# S7_Misc.net
KiCad netlist of a schematic drawn in Altium Designer
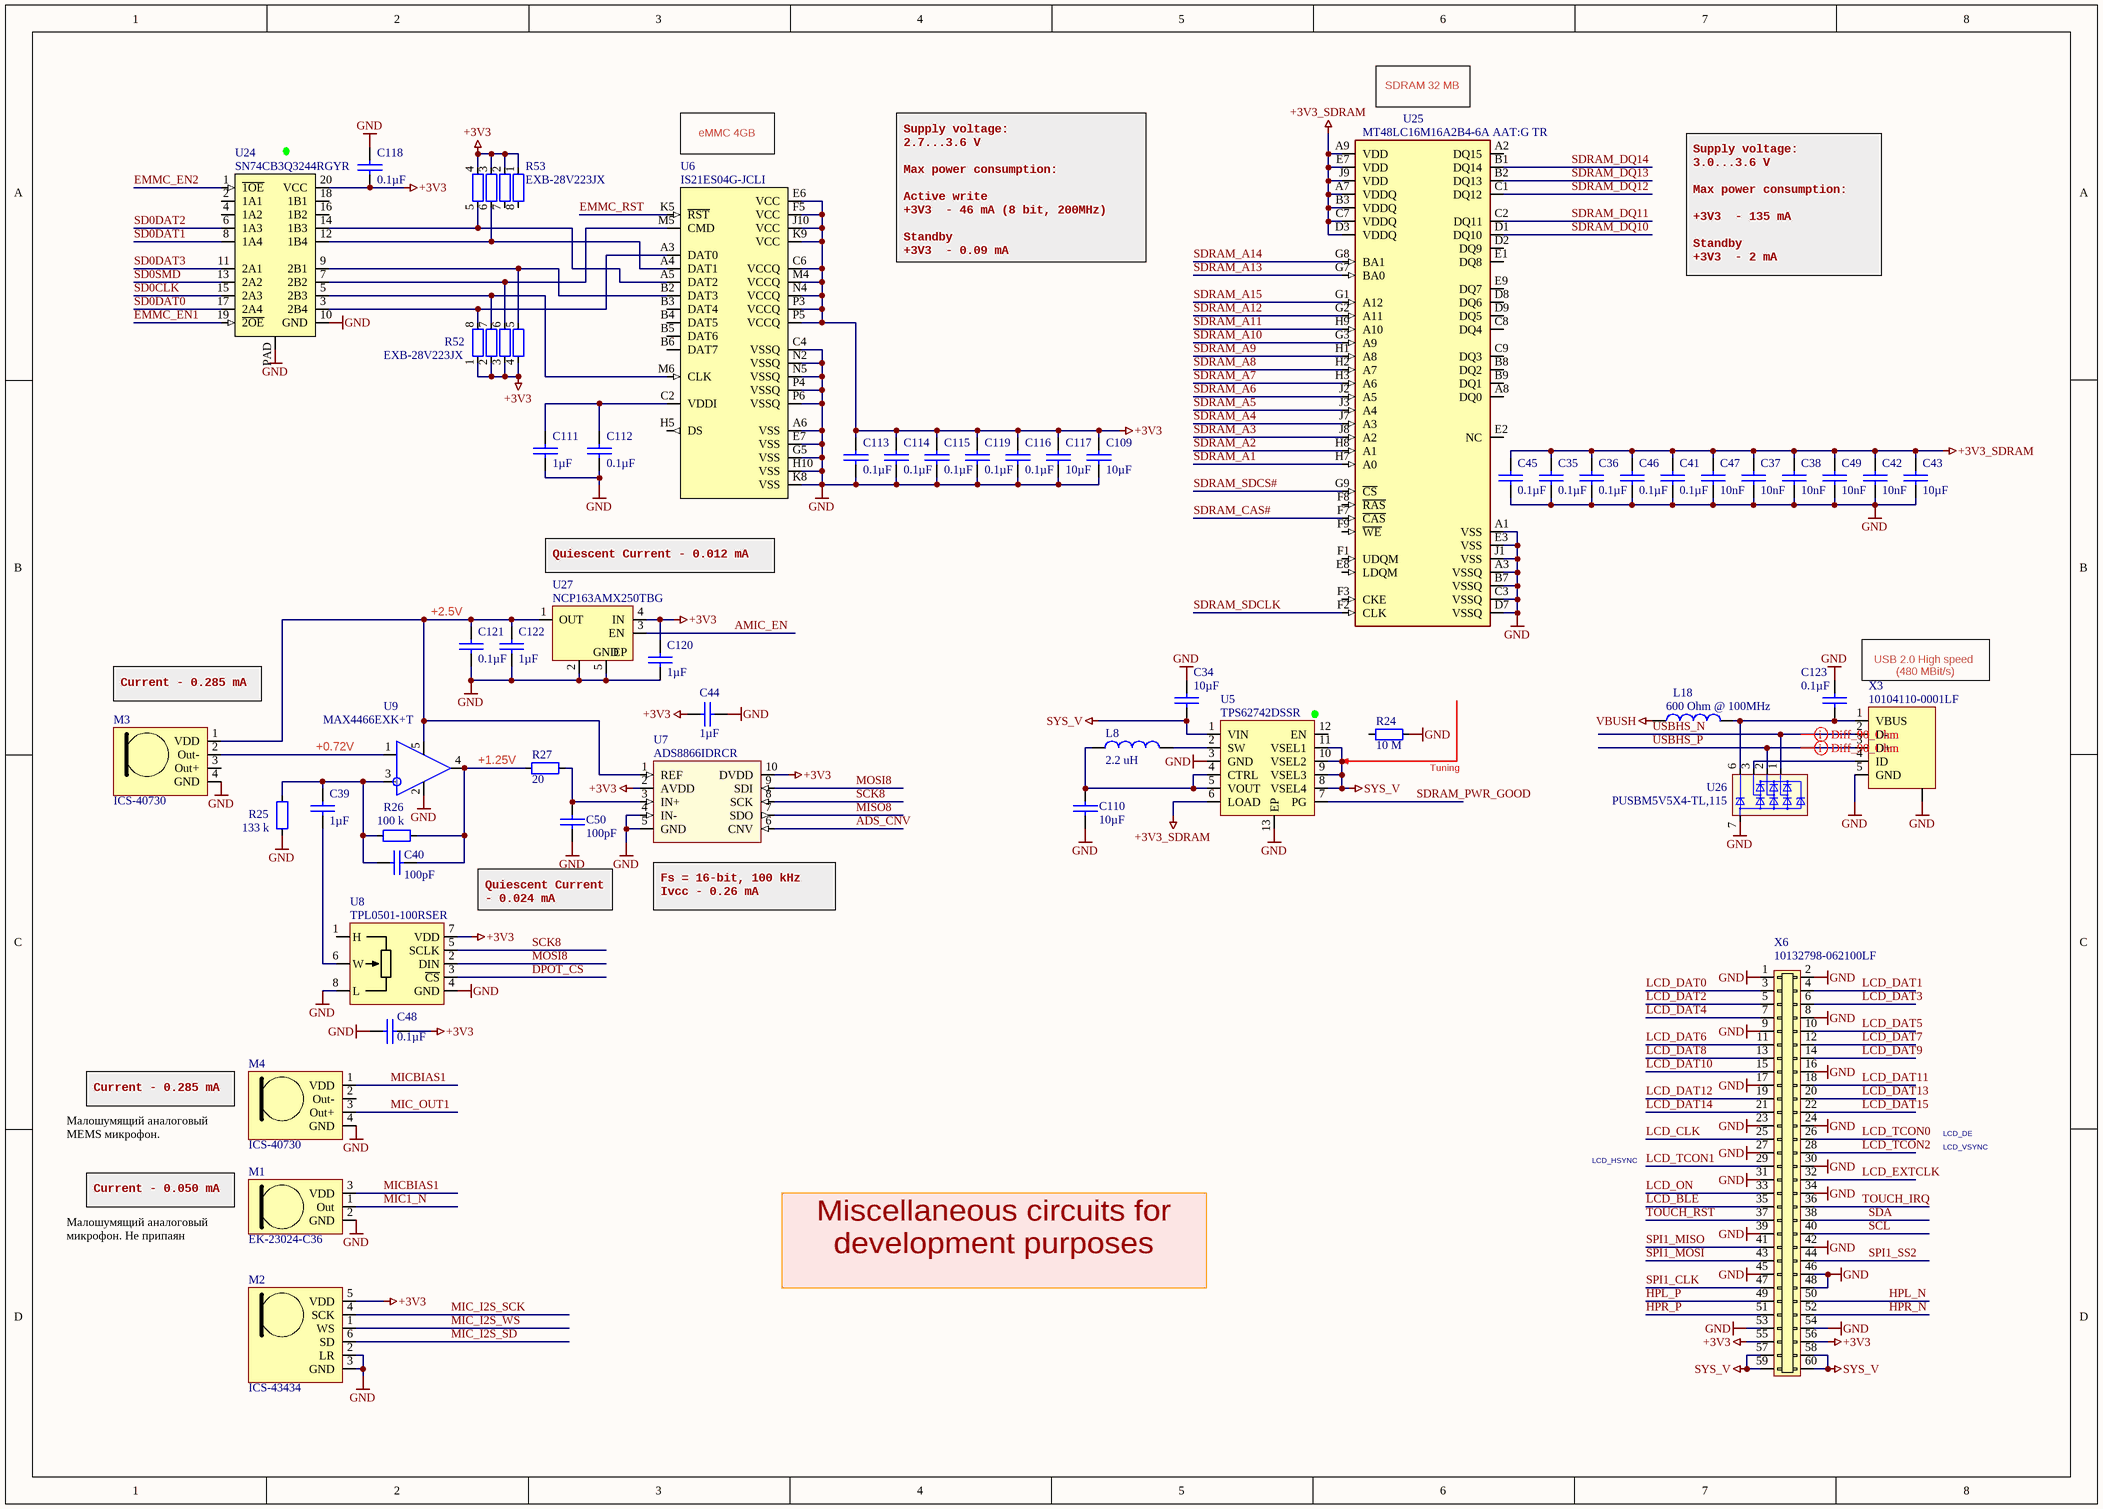
[diagram p0: S7_Misc.SchDoc]

(export (version "E")
  (design (tool "Eeschema 10.0.6"))
  (components
    (comp (ref "C34")
      (value "10µF")
      (footprint "0603 CAP")
      (description "10µF, ±10%, 16V, X5R, 0603 (1608 Metric), -55°C ~ 85°C, -, Automotive")
      (fields
        (field (name "PART NUMBER") "GRT188R61C106KE13D")
        (field (name "MANUFACTURER") "Murata Electronics North America")
      )
      (libsource (lib "ea_PassivComps") (part "Capacitor"))
    )
    (comp (ref "C35")
      (value "0.1µF")
      (footprint "0402 CAP")
      (description "0.1µF, ±10%, 50V, X7R, 0402 (1005 Metric), -55°C ~ 125°C, -, General Purpose")
      (fields
        (field (name "PART NUMBER") "0402B104K500CT")
        (field (name "MANUFACTURER") "Walsin Technology Corporation")
      )
      (libsource (lib "ea_PassivComps") (part "Capacitor"))
    )
    (comp (ref "C36")
      (value "0.1µF")
      (footprint "0402 CAP")
      (description "0.1µF, ±10%, 50V, X7R, 0402 (1005 Metric), -55°C ~ 125°C, -, General Purpose")
      (fields
        (field (name "PART NUMBER") "0402B104K500CT")
        (field (name "MANUFACTURER") "Walsin Technology Corporation")
      )
      (libsource (lib "ea_PassivComps") (part "Capacitor"))
    )
    (comp (ref "C37")
      (value "10nF")
      (footprint "0402 CAP")
      (description "10000pF, ±10%, 50V, X7R, 0402 (1005 Metric), -55°C ~ 125°C, -, General Purpose")
      (fields
        (field (name "PART NUMBER") "CL05B103KB5NNNC")
        (field (name "MANUFACTURER") "Samsung Electro-Mechanics")
      )
      (libsource (lib "ea_PassivComps") (part "Capacitor"))
    )
    (comp (ref "C38")
      (value "10nF")
      (footprint "0402 CAP")
      (description "10000pF, ±10%, 50V, X7R, 0402 (1005 Metric), -55°C ~ 125°C, -, General Purpose")
      (fields
        (field (name "PART NUMBER") "CL05B103KB5NNNC")
        (field (name "MANUFACTURER") "Samsung Electro-Mechanics")
      )
      (libsource (lib "ea_PassivComps") (part "Capacitor"))
    )
    (comp (ref "C39")
      (value "1µF")
      (footprint "0402 CAP")
      (description "1µF, ±20%, 25V, X5R, 0402 (1005 Metric), -55°C ~ 85°C, -, General Purpose")
      (fields (field (name "PART NUMBER") "TMK105BJ105MV-F") (field (name "MANUFACTURER") "Taiyo Yuden"))
      (libsource (lib "ea_PassivComps") (part "Capacitor"))
    )
    (comp (ref "C40")
      (value "100pF")
      (footprint "0402 CAP")
      (description "100pF, ±5%, 50V, C0G, NP0, 0402 (1005 Metric), -55°C ~ 125°C, -, Automotive")
      (fields (field (name "PART NUMBER") "AC0402JRNPO9BN101") (field (name "MANUFACTURER") "Yageo"))
      (libsource (lib "ea_PassivComps") (part "Capacitor"))
    )
    (comp (ref "C41")
      (value "0.1µF")
      (footprint "0402 CAP")
      (description "0.1µF, ±10%, 50V, X7R, 0402 (1005 Metric), -55°C ~ 125°C, -, General Purpose")
      (fields
        (field (name "PART NUMBER") "0402B104K500CT")
        (field (name "MANUFACTURER") "Walsin Technology Corporation")
      )
      (libsource (lib "ea_PassivComps") (part "Capacitor"))
    )
    (comp (ref "C42")
      (value "10nF")
      (footprint "0402 CAP")
      (description "10000pF, ±10%, 50V, X7R, 0402 (1005 Metric), -55°C ~ 125°C, -, General Purpose")
      (fields
        (field (name "PART NUMBER") "CL05B103KB5NNNC")
        (field (name "MANUFACTURER") "Samsung Electro-Mechanics")
      )
      (libsource (lib "ea_PassivComps") (part "Capacitor"))
    )
    (comp (ref "C43")
      (value "10µF")
      (footprint "0603 CAP")
      (description "10µF, ±10%, 16V, X5R, 0603 (1608 Metric), -55°C ~ 85°C, -, Automotive")
      (fields
        (field (name "PART NUMBER") "GRT188R61C106KE13D")
        (field (name "MANUFACTURER") "Murata Electronics North America")
      )
      (libsource (lib "ea_PassivComps") (part "Capacitor"))
    )
    (comp (ref "C44")
      (value "1µF")
      (footprint "0402 CAP")
      (description "1µF, ±20%, 25V, X5R, 0402 (1005 Metric), -55°C ~ 85°C, -, General Purpose")
      (fields (field (name "PART NUMBER") "TMK105BJ105MV-F") (field (name "MANUFACTURER") "Taiyo Yuden"))
      (libsource (lib "ea_PassivComps") (part "Capacitor"))
    )
    (comp (ref "C45")
      (value "0.1µF")
      (footprint "0402 CAP")
      (description "0.1µF, ±10%, 50V, X7R, 0402 (1005 Metric), -55°C ~ 125°C, -, General Purpose")
      (fields
        (field (name "PART NUMBER") "0402B104K500CT")
        (field (name "MANUFACTURER") "Walsin Technology Corporation")
      )
      (libsource (lib "ea_PassivComps") (part "Capacitor"))
    )
    (comp (ref "C46")
      (value "0.1µF")
      (footprint "0402 CAP")
      (description "0.1µF, ±10%, 50V, X7R, 0402 (1005 Metric), -55°C ~ 125°C, -, General Purpose")
      (fields
        (field (name "PART NUMBER") "0402B104K500CT")
        (field (name "MANUFACTURER") "Walsin Technology Corporation")
      )
      (libsource (lib "ea_PassivComps") (part "Capacitor"))
    )
    (comp (ref "C47")
      (value "10nF")
      (footprint "0402 CAP")
      (description "10000pF, ±10%, 50V, X7R, 0402 (1005 Metric), -55°C ~ 125°C, -, General Purpose")
      (fields
        (field (name "PART NUMBER") "CL05B103KB5NNNC")
        (field (name "MANUFACTURER") "Samsung Electro-Mechanics")
      )
      (libsource (lib "ea_PassivComps") (part "Capacitor"))
    )
    (comp (ref "C48")
      (value "0.1µF")
      (footprint "0402 CAP")
      (description "0.1µF, ±10%, 50V, X7R, 0402 (1005 Metric), -55°C ~ 125°C, -, General Purpose")
      (fields
        (field (name "PART NUMBER") "0402B104K500CT")
        (field (name "MANUFACTURER") "Walsin Technology Corporation")
      )
      (libsource (lib "ea_PassivComps") (part "Capacitor"))
    )
    (comp (ref "C49")
      (value "10nF")
      (footprint "0402 CAP")
      (description "10000pF, ±10%, 50V, X7R, 0402 (1005 Metric), -55°C ~ 125°C, -, General Purpose")
      (fields
        (field (name "PART NUMBER") "CL05B103KB5NNNC")
        (field (name "MANUFACTURER") "Samsung Electro-Mechanics")
      )
      (libsource (lib "ea_PassivComps") (part "Capacitor"))
    )
    (comp (ref "C50")
      (value "100pF")
      (footprint "0402 CAP")
      (description "100pF, ±5%, 50V, C0G, NP0, 0402 (1005 Metric), -55°C ~ 125°C, -, Automotive")
      (fields (field (name "PART NUMBER") "AC0402JRNPO9BN101") (field (name "MANUFACTURER") "Yageo"))
      (libsource (lib "ea_PassivComps") (part "Capacitor"))
    )
    (comp (ref "C109")
      (value "10µF")
      (footprint "0603 CAP")
      (description "10µF, ±10%, 16V, X5R, 0603 (1608 Metric), -55°C ~ 85°C, -, Automotive")
      (fields
        (field (name "PART NUMBER") "GRT188R61C106KE13D")
        (field (name "MANUFACTURER") "Murata Electronics North America")
      )
      (libsource (lib "ea_PassivComps") (part "Capacitor"))
    )
    (comp (ref "C110")
      (value "10µF")
      (footprint "0603 CAP")
      (description "10µF, ±10%, 16V, X5R, 0603 (1608 Metric), -55°C ~ 85°C, -, Automotive")
      (fields
        (field (name "PART NUMBER") "GRT188R61C106KE13D")
        (field (name "MANUFACTURER") "Murata Electronics North America")
      )
      (libsource (lib "ea_PassivComps") (part "Capacitor"))
    )
    (comp (ref "C111")
      (value "1µF")
      (footprint "0402 CAP")
      (description "1µF, ±20%, 25V, X5R, 0402 (1005 Metric), -55°C ~ 85°C, -, General Purpose")
      (fields (field (name "PART NUMBER") "TMK105BJ105MV-F") (field (name "MANUFACTURER") "Taiyo Yuden"))
      (libsource (lib "ea_PassivComps") (part "Capacitor"))
    )
    (comp (ref "C112")
      (value "0.1µF")
      (footprint "0402 CAP")
      (description "0.1µF, ±10%, 50V, X7R, 0402 (1005 Metric), -55°C ~ 125°C, -, General Purpose")
      (fields
        (field (name "PART NUMBER") "0402B104K500CT")
        (field (name "MANUFACTURER") "Walsin Technology Corporation")
      )
      (libsource (lib "ea_PassivComps") (part "Capacitor"))
    )
    (comp (ref "C113")
      (value "0.1µF")
      (footprint "0402 CAP")
      (description "0.1µF, ±10%, 50V, X7R, 0402 (1005 Metric), -55°C ~ 125°C, -, General Purpose")
      (fields
        (field (name "PART NUMBER") "0402B104K500CT")
        (field (name "MANUFACTURER") "Walsin Technology Corporation")
      )
      (libsource (lib "ea_PassivComps") (part "Capacitor"))
    )
    (comp (ref "C114")
      (value "0.1µF")
      (footprint "0402 CAP")
      (description "0.1µF, ±10%, 50V, X7R, 0402 (1005 Metric), -55°C ~ 125°C, -, General Purpose")
      (fields
        (field (name "PART NUMBER") "0402B104K500CT")
        (field (name "MANUFACTURER") "Walsin Technology Corporation")
      )
      (libsource (lib "ea_PassivComps") (part "Capacitor"))
    )
    (comp (ref "C115")
      (value "0.1µF")
      (footprint "0402 CAP")
      (description "0.1µF, ±10%, 50V, X7R, 0402 (1005 Metric), -55°C ~ 125°C, -, General Purpose")
      (fields
        (field (name "PART NUMBER") "0402B104K500CT")
        (field (name "MANUFACTURER") "Walsin Technology Corporation")
      )
      (libsource (lib "ea_PassivComps") (part "Capacitor"))
    )
    (comp (ref "C116")
      (value "0.1µF")
      (footprint "0402 CAP")
      (description "0.1µF, ±10%, 50V, X7R, 0402 (1005 Metric), -55°C ~ 125°C, -, General Purpose")
      (fields
        (field (name "PART NUMBER") "0402B104K500CT")
        (field (name "MANUFACTURER") "Walsin Technology Corporation")
      )
      (libsource (lib "ea_PassivComps") (part "Capacitor"))
    )
    (comp (ref "C117")
      (value "10µF")
      (footprint "0603 CAP")
      (description "10µF, ±10%, 16V, X5R, 0603 (1608 Metric), -55°C ~ 85°C, -, Automotive")
      (fields
        (field (name "PART NUMBER") "GRT188R61C106KE13D")
        (field (name "MANUFACTURER") "Murata Electronics North America")
      )
      (libsource (lib "ea_PassivComps") (part "Capacitor"))
    )
    (comp (ref "C118")
      (value "0.1µF")
      (footprint "0402 CAP")
      (description "0.1µF, ±10%, 50V, X7R, 0402 (1005 Metric), -55°C ~ 125°C, -, General Purpose")
      (fields
        (field (name "PART NUMBER") "0402B104K500CT")
        (field (name "MANUFACTURER") "Walsin Technology Corporation")
      )
      (libsource (lib "ea_PassivComps") (part "Capacitor"))
    )
    (comp (ref "C119")
      (value "0.1µF")
      (footprint "0402 CAP")
      (description "0.1µF, ±10%, 50V, X7R, 0402 (1005 Metric), -55°C ~ 125°C, -, General Purpose")
      (fields
        (field (name "PART NUMBER") "0402B104K500CT")
        (field (name "MANUFACTURER") "Walsin Technology Corporation")
      )
      (libsource (lib "ea_PassivComps") (part "Capacitor"))
    )
    (comp (ref "C120")
      (value "1µF")
      (footprint "0402 CAP")
      (description "1µF, ±20%, 25V, X5R, 0402 (1005 Metric), -55°C ~ 85°C, -, General Purpose")
      (fields (field (name "PART NUMBER") "TMK105BJ105MV-F") (field (name "MANUFACTURER") "Taiyo Yuden"))
      (libsource (lib "ea_PassivComps") (part "Capacitor"))
    )
    (comp (ref "C121")
      (value "0.1µF")
      (footprint "0402 CAP")
      (description "0.1µF, ±10%, 50V, X7R, 0402 (1005 Metric), -55°C ~ 125°C, -, General Purpose")
      (fields
        (field (name "PART NUMBER") "0402B104K500CT")
        (field (name "MANUFACTURER") "Walsin Technology Corporation")
      )
      (libsource (lib "ea_PassivComps") (part "Capacitor"))
    )
    (comp (ref "C122")
      (value "1µF")
      (footprint "0402 CAP")
      (description "1µF, ±20%, 25V, X5R, 0402 (1005 Metric), -55°C ~ 85°C, -, General Purpose")
      (fields (field (name "PART NUMBER") "TMK105BJ105MV-F") (field (name "MANUFACTURER") "Taiyo Yuden"))
      (libsource (lib "ea_PassivComps") (part "Capacitor"))
    )
    (comp (ref "C123")
      (value "0.1µF")
      (footprint "0402 CAP")
      (description "0.1µF, ±10%, 50V, X7R, 0402 (1005 Metric), -55°C ~ 125°C, -, General Purpose")
      (fields
        (field (name "PART NUMBER") "0402B104K500CT")
        (field (name "MANUFACTURER") "Walsin Technology Corporation")
      )
      (libsource (lib "ea_PassivComps") (part "Capacitor"))
    )
    (comp (ref "L8")
      (value "2.2 uH")
      (footprint "744025002")
      (description "Inductors 2.2 uH, 1.8 A, 0.066 Ohms, ±20% -40°C ~ 125°C, 2.8 x 2.8 mm")
      (fields (field (name "MANUFACTURER") "Wurth Electronics Inc") (field (name "PARTNUM") "732-2613-1-ND"))
      (libsource (lib "ea_Inductors") (part "744025002"))
    )
    (comp (ref "L18")
      (value "600 Ohm @ 100MHz")
      (footprint "0805")
      (description "FERRITE BEAD 600 OHM, 0805, -55°C ~ 125°C")
      (fields (field (name "MANUFACTURER") "TDK Corporation") (field (name "PARTNUM") "445-2206-1-ND"))
      (libsource (lib "ea_Inductors") (part "MPZ2012S601AT000"))
    )
    (comp (ref "M1")
      (value "EK-23024-C36")
      (footprint "EK-23024-C36")
      (fields (field (name "MANUFACTURER") "Knowles") (field (name "PARTNUM") "423-1121-ND"))
      (libsource (lib "ea_Sound_devices") (part "EK-23024-C36"))
    )
    (comp (ref "M2")
      (value "ICS-43434")
      (footprint "ICS-43434")
      (fields (field (name "MANUFACTURER") "TDK InvenSense") (field (name "PARTNUM") "1428-1066-1-ND"))
      (libsource (lib "ea_Sound_devices") (part "ICS-43434"))
    )
    (comp (ref "M3")
      (value "ICS-40730")
      (footprint "ICS-40730")
      (fields (field (name "MANUFACTURER") "TDK InvenSense") (field (name "PARTNUM") "1428-1141-1-ND"))
      (libsource (lib "ea_Sound_devices") (part "ICS-40730"))
    )
    (comp (ref "M4")
      (value "ICS-40730")
      (footprint "ICS-40730")
      (fields (field (name "MANUFACTURER") "TDK InvenSense") (field (name "PARTNUM") "1428-1141-1-ND"))
      (libsource (lib "ea_Sound_devices") (part "ICS-40730"))
    )
    (comp (ref "R24")
      (value "10 M")
      (footprint "0402")
      (description "10 MOhms, ±1%, 0.063W, 1/16W, Thick Film, ±100ppm/°C, 0402 (1005 Metric), -55°C ~ 155°C, -")
      (fields (field (name "MANUFACTURER") "Vishay Dale") (field (name "TOLERANCE") "±1%"))
      (libsource (lib "ea_PassivComps") (part "Resistor"))
    )
    (comp (ref "R25")
      (value "133 k")
      (footprint "0402")
      (fields
        (field (name "MANUFACTURER") "Stackpole Electronics Inc")
        (field (name "TOLERANCE") "±1%")
        (field (name "VOLTAGE") "75V")
      )
      (libsource (lib "") (part "Resistor_1"))
    )
    (comp (ref "R26")
      (value "100 k")
      (footprint "0402")
      (fields
        (field (name "MANUFACTURER") "Stackpole Electronics Inc")
        (field (name "TOLERANCE") "±1%")
        (field (name "VOLTAGE") "75V")
      )
      (libsource (lib "ea_PassivComps") (part "Resistor"))
    )
    (comp (ref "R27")
      (value "20")
      (footprint "0402")
      (fields
        (field (name "MANUFACTURER") "Stackpole Electronics Inc")
        (field (name "TOLERANCE") "±1%")
        (field (name "VOLTAGE") "75V")
      )
      (libsource (lib "ea_PassivComps") (part "Resistor"))
    )
    (comp (ref "R52")
      (value "EXB-28V223JX")
      (footprint "EXB28V 2x1 mm")
      (description "22k Ohm ±5%,  4 Resistor, -55°C ~ 125°C,(2.00mm x 1.00mm)")
      (fields (field (name "MANUFACTURER") "Panasonic Electronic Components") (field (name "TOLERANCE") "5%"))
      (libsource (lib "ea_Resistors") (part "EXB-28V223JX"))
    )
    (comp (ref "R53")
      (value "EXB-28V223JX")
      (footprint "EXB28V 2x1 mm")
      (description "22k Ohm ±5%,  4 Resistor, -55°C ~ 125°C,(2.00mm x 1.00mm)")
      (fields (field (name "MANUFACTURER") "Panasonic Electronic Components") (field (name "TOLERANCE") "5%"))
      (libsource (lib "") (part "EXB-28V223JX_1"))
    )
    (comp (ref "U5")
      (value "TPS62742DSSR")
      (footprint "12-WSON")
      (description "DCDC 1.8-3.3V, 400mA , Iq=360nA, -40°C ~ 85°C, 12-WSON (3x2)")
      (fields (field (name "MANUFACTURER") "Texas Instruments") (field (name "PARTNUM") "296-40852-1-ND"))
      (libsource (lib "ea_IC_Power_Reg_Ref_Sw") (part "TPS62742DSSR"))
    )
    (comp (ref "U6")
      (value "IS21ES04G-JCLI")
      (footprint "MICRON_WFBGA153")
      (description "4GByte eMMC, 200MHz, 2.7V ~ 3.6V, 153-VFBGA (11.5x13),  -40°C ~ 85°C")
      (fields
        (field (name "MANUFACTURER") "Integrated Silicon Solution Inc")
        (field (name "DISPLAY NAME") "IS21ES04G-JCLI")
      )
      (libsource (lib "ea_IC_NOR_NAND_FLASH") (part "IS21ES04G-JCLI"))
    )
    (comp (ref "U7")
      (value "ADS8866IDRCR")
      (footprint "TI S-PVSON-N10")
      (description "16-bit ADC, 100k, Pseudo-Differential, Single Ended, 2.7..3.6V,  -40°C...85°C, 10-VSON")
      (fields (field (name "MANUFACTURER") "Texas Instruments") (field (name "PARTNUM") "296-39886-1-ND"))
      (libsource (lib "ea_IC_ADC") (part "ADS8866IDRCR"))
    )
    (comp (ref "U8")
      (value "TPL0501-100RSER")
      (footprint "UQFN-8")
      (description "Digital Potentiometer 100k Ohm 1 Circuit 256 Taps SPI Interface, -40°C ~ 125°C,  8-UQFN (1.5x1.5)")
      (fields (field (name "MANUFACTURER") "Texas Instruments") (field (name "PARTNUM") "296-29585-1-ND"))
      (libsource (lib "ea_IC_Digital_Potentiometers") (part "TPL0501-100RSER"))
    )
    (comp (ref "U9")
      (value "MAX4466EXK+T")
      (footprint "SOT-353 ON Semi")
      (description "OpAmp, Class AB,  2.4V ~ 5.5V, -40°C ~ 85°C, SC-70-5")
      (fields (field (name "MANUFACTURER") "Maxim Integrated") (field (name "PARTNUM") "MAX4466EXK+CT-ND"))
      (libsource (lib "ea_IC_OPAmps_AnComparators") (part "MAX4466EXK+T"))
    )
    (comp (ref "U24")
      (value "SN74CB3Q3244RGYR")
      (footprint "TI_PVQFN-N20")
      (description "Bus Switch 4 x 1:1, 2.3V ~ 3.6V,  -40°C ~ 85°C, 20-VQFN (3.5x4.5)")
      (fields (field (name "MANUFACTURER") "Texas Instruments") (field (name "PARTNUM") "296-19127-1-ND"))
      (libsource (lib "ea_IC_registers_buffers") (part "SN74CB3Q3244RGYR"))
    )
    (comp (ref "U25")
      (value "MT48LC16M16A2B4-6A AAT:G TR")
      (footprint "MICRON_VFBGA54")
      (description "Micron SDRAM 256M-Bit 16Mx16, 3.3V, 167MHz, 5.4ns, -40°C ~ 105°C, 54-VFBGA (8x8)")
      (fields (field (name "MANUFACTURER") "Micron Technology Inc.") (field (name "PARTNUM") "557-1932-1-ND"))
      (libsource (lib "ea_IC_RAM") (part "MT48LC16M16A2B4-6A AAT{colon}G TR"))
    )
    (comp (ref "U26")
      (value "PUSBM5V5X4-TL,115")
      (footprint "DFN1616-6")
      (description "TVS DIODE 5.5VWM 12VC 6HXSON")
      (fields (field (name "MANUFACTURER") "NXP Semiconductors") (field (name "PARTNUM") "568-10921-1-ND"))
      (libsource (lib "ea_TVS_protection") (part "PUSBM5V5X4-TL,115"))
    )
    (comp (ref "U27")
      (value "NCP163AMX250TBG")
      (footprint "4-XDFN")
      (description "LDO 2.5V, 250 mA, Vin < 5.5V, Iq < 20uA, -40..+125 C,  4-XDFN (1x1)")
      (fields
        (field (name "MANUFACTURER") "ON Semiconductor")
        (field (name "PARTNUM") "NCP163AMX250TBGOSCT-ND")
      )
      (libsource (lib "ea_IC_Power_Reg_Ref_Sw") (part "NCP163AMX250TBG"))
    )
    (comp (ref "X3")
      (value "10104110-0001LF")
      (footprint "FCI micro USB B receptacle SMD")
      (description "USB - micro B USB 2.0 Receptacle Connector 5 Position Surface Mount, Right Angle")
      (fields (field (name "MANUFACTURER") "Amphenol FCI") (field (name "PARTNUM") "609-4052-1-ND"))
      (libsource (lib "ea_Connectors_USB") (part "10104110-0001LF"))
    )
    (comp (ref "X6")
      (value "10132798-062100LF")
      (footprint "10132798-062100LF")
      (fields (field (name "MANUFACTURER") "Amphenol ICC (FCI)") (field (name "PARTNUM") "609-5230-1-ND"))
      (libsource (lib "ea_Connectors_0.5_mm_pitch") (part "10132798-062100LF"))
    )
  )
  (nets
    (net (code "1") (name "+3V3") (class "Default")
      (node (ref "C109") (pin "1") (pinfunction "1_1") (pintype "passive"))
      (node (ref "C113") (pin "1") (pinfunction "1_1") (pintype "passive"))
      (node (ref "C114") (pin "1") (pinfunction "1_1") (pintype "passive"))
      (node (ref "C115") (pin "1") (pinfunction "1_1") (pintype "passive"))
      (node (ref "C116") (pin "1") (pinfunction "1_1") (pintype "passive"))
      (node (ref "C117") (pin "1") (pinfunction "1_1") (pintype "passive"))
      (node (ref "C118") (pin "2") (pinfunction "2_2") (pintype "passive"))
      (node (ref "C119") (pin "1") (pinfunction "1_1") (pintype "passive"))
      (node (ref "C120") (pin "1") (pinfunction "1_1") (pintype "passive"))
      (node (ref "C44") (pin "1") (pinfunction "1_1") (pintype "passive"))
      (node (ref "C48") (pin "2") (pinfunction "2_2") (pintype "passive"))
      (node (ref "M2") (pin "5") (pinfunction "VDD_5") (pintype "passive"))
      (node (ref "R52") (pin "1") (pinfunction "1_1") (pintype "passive"))
      (node (ref "R52") (pin "2") (pinfunction "2_2") (pintype "passive"))
      (node (ref "R52") (pin "3") (pinfunction "3_3") (pintype "passive"))
      (node (ref "R52") (pin "4") (pinfunction "4_4") (pintype "passive"))
      (node (ref "R53") (pin "1") (pinfunction "1_1") (pintype "passive"))
      (node (ref "R53") (pin "2") (pinfunction "2_2") (pintype "passive"))
      (node (ref "R53") (pin "3") (pinfunction "3_3") (pintype "passive"))
      (node (ref "R53") (pin "4") (pinfunction "4_4") (pintype "passive"))
      (node (ref "U24") (pin "20") (pinfunction "VCC_20") (pintype "power_in"))
      (node (ref "U27") (pin "4") (pinfunction "IN_4") (pintype "power_in"))
      (node (ref "U6") (pin "C6") (pinfunction "VCCQ_C6") (pintype "power_in"))
      (node (ref "U6") (pin "E6") (pinfunction "VCC_E6") (pintype "power_in"))
      (node (ref "U6") (pin "F5") (pinfunction "VCC_F5") (pintype "power_in"))
      (node (ref "U6") (pin "J10") (pinfunction "VCC_J10") (pintype "power_in"))
      (node (ref "U6") (pin "K9") (pinfunction "VCC_K9") (pintype "power_in"))
      (node (ref "U6") (pin "M4") (pinfunction "VCCQ_M4") (pintype "power_in"))
      (node (ref "U6") (pin "N4") (pinfunction "VCCQ_N4") (pintype "power_in"))
      (node (ref "U6") (pin "P3") (pinfunction "VCCQ_P3") (pintype "power_in"))
      (node (ref "U6") (pin "P5") (pinfunction "VCCQ_P5") (pintype "power_in"))
      (node (ref "U7") (pin "10") (pinfunction "DVDD_10") (pintype "power_in"))
      (node (ref "U7") (pin "2") (pinfunction "AVDD_2") (pintype "power_in"))
      (node (ref "U8") (pin "7") (pinfunction "VDD_7") (pintype "passive"))
      (node (ref "X6") (pin "55") (pinfunction "28_55") (pintype "passive"))
      (node (ref "X6") (pin "56") (pinfunction "29_56") (pintype "passive"))
    )
    (net (code "2") (name "+3V3_SDRAM") (class "Default")
      (node (ref "C35") (pin "1") (pinfunction "1_1") (pintype "passive"))
      (node (ref "C36") (pin "1") (pinfunction "1_1") (pintype "passive"))
      (node (ref "C37") (pin "1") (pinfunction "1_1") (pintype "passive"))
      (node (ref "C38") (pin "1") (pinfunction "1_1") (pintype "passive"))
      (node (ref "C41") (pin "1") (pinfunction "1_1") (pintype "passive"))
      (node (ref "C42") (pin "1") (pinfunction "1_1") (pintype "passive"))
      (node (ref "C43") (pin "1") (pinfunction "1_1") (pintype "passive"))
      (node (ref "C45") (pin "1") (pinfunction "1_1") (pintype "passive"))
      (node (ref "C46") (pin "1") (pinfunction "1_1") (pintype "passive"))
      (node (ref "C47") (pin "1") (pinfunction "1_1") (pintype "passive"))
      (node (ref "C49") (pin "1") (pinfunction "1_1") (pintype "passive"))
      (node (ref "U25") (pin "A7") (pinfunction "VDDQ_A7") (pintype "power_in"))
      (node (ref "U25") (pin "A9") (pinfunction "VDD_A9") (pintype "power_in"))
      (node (ref "U25") (pin "B3") (pinfunction "VDDQ_B3") (pintype "power_in"))
      (node (ref "U25") (pin "C7") (pinfunction "VDDQ_C7") (pintype "power_in"))
      (node (ref "U25") (pin "D3") (pinfunction "VDDQ_D3") (pintype "power_in"))
      (node (ref "U25") (pin "E7") (pinfunction "VDD_E7") (pintype "power_in"))
      (node (ref "U25") (pin "J9") (pinfunction "VDD_J9") (pintype "power_in"))
      (node (ref "U5") (pin "6") (pinfunction "LOAD_6") (pintype "passive"))
    )
    (net (code "3") (name "/ADS_CNV") (class "Default")
      (node (ref "U7") (pin "6") (pinfunction "CNV_6") (pintype "input"))
    )
    (net (code "4") (name "/AMIC_EN") (class "Default")
      (node (ref "U27") (pin "3") (pinfunction "EN_3") (pintype "power_in"))
    )
    (net (code "5") (name "/DPOT_CS") (class "Default")
      (node (ref "U8") (pin "3") (pinfunction "~{CS}_3") (pintype "passive"))
    )
    (net (code "6") (name "/EMMC_EN1") (class "Default")
      (node (ref "U24") (pin "19") (pinfunction "~{2OE}_19") (pintype "input"))
    )
    (net (code "7") (name "/EMMC_EN2") (class "Default")
      (node (ref "U24") (pin "1") (pinfunction "~{1OE}_1") (pintype "input"))
    )
    (net (code "8") (name "/EMMC_RST") (class "Default")
      (node (ref "U6") (pin "K5") (pinfunction "~{RST}_K5") (pintype "input"))
    )
    (net (code "9") (name "/HPL_N") (class "Default")
      (node (ref "X6") (pin "50") (pinfunction "26_50") (pintype "passive"))
    )
    (net (code "10") (name "/HPL_P") (class "Default")
      (node (ref "X6") (pin "49") (pinfunction "25_49") (pintype "passive"))
    )
    (net (code "11") (name "/HPR_N") (class "Default")
      (node (ref "X6") (pin "52") (pinfunction "27_52") (pintype "passive"))
    )
    (net (code "12") (name "/HPR_P") (class "Default")
      (node (ref "X6") (pin "51") (pinfunction "26_51") (pintype "passive"))
    )
    (net (code "13") (name "/LCD_BLE") (class "Default")
      (node (ref "X6") (pin "35") (pinfunction "18_35") (pintype "passive"))
    )
    (net (code "14") (name "/LCD_CLK") (class "Default")
      (node (ref "X6") (pin "25") (pinfunction "13_25") (pintype "passive"))
    )
    (net (code "15") (name "/LCD_DAT0") (class "Default")
      (node (ref "X6") (pin "3") (pinfunction "2_3") (pintype "passive"))
    )
    (net (code "16") (name "/LCD_DAT1") (class "Default")
      (node (ref "X6") (pin "4") (pinfunction "3_4") (pintype "passive"))
    )
    (net (code "17") (name "/LCD_DAT2") (class "Default")
      (node (ref "X6") (pin "5") (pinfunction "3_5") (pintype "passive"))
    )
    (net (code "18") (name "/LCD_DAT3") (class "Default")
      (node (ref "X6") (pin "6") (pinfunction "4_6") (pintype "passive"))
    )
    (net (code "19") (name "/LCD_DAT4") (class "Default")
      (node (ref "X6") (pin "7") (pinfunction "4_7") (pintype "passive"))
    )
    (net (code "20") (name "/LCD_DAT5") (class "Default")
      (node (ref "X6") (pin "10") (pinfunction "6_10") (pintype "passive"))
    )
    (net (code "21") (name "/LCD_DAT6") (class "Default")
      (node (ref "X6") (pin "11") (pinfunction "6_11") (pintype "passive"))
    )
    (net (code "22") (name "/LCD_DAT7") (class "Default")
      (node (ref "X6") (pin "12") (pinfunction "7_12") (pintype "passive"))
    )
    (net (code "23") (name "/LCD_DAT8") (class "Default")
      (node (ref "X6") (pin "13") (pinfunction "7_13") (pintype "passive"))
    )
    (net (code "24") (name "/LCD_DAT9") (class "Default")
      (node (ref "X6") (pin "14") (pinfunction "8_14") (pintype "passive"))
    )
    (net (code "25") (name "/LCD_DAT10") (class "Default")
      (node (ref "X6") (pin "15") (pinfunction "8_15") (pintype "passive"))
    )
    (net (code "26") (name "/LCD_DAT11") (class "Default")
      (node (ref "X6") (pin "18") (pinfunction "10_18") (pintype "passive"))
    )
    (net (code "27") (name "/LCD_DAT12") (class "Default")
      (node (ref "X6") (pin "19") (pinfunction "10_19") (pintype "passive"))
    )
    (net (code "28") (name "/LCD_DAT13") (class "Default")
      (node (ref "X6") (pin "20") (pinfunction "11_20") (pintype "passive"))
    )
    (net (code "29") (name "/LCD_DAT14") (class "Default")
      (node (ref "X6") (pin "21") (pinfunction "11_21") (pintype "passive"))
    )
    (net (code "30") (name "/LCD_DAT15") (class "Default")
      (node (ref "X6") (pin "22") (pinfunction "12_22") (pintype "passive"))
    )
    (net (code "31") (name "/LCD_EXTCLK") (class "Default")
      (node (ref "X6") (pin "32") (pinfunction "17_32") (pintype "passive"))
    )
    (net (code "32") (name "/LCD_ON") (class "Default")
      (node (ref "X6") (pin "33") (pinfunction "17_33") (pintype "passive"))
    )
    (net (code "33") (name "/LCD_TCON0") (class "Default")
      (node (ref "X6") (pin "26") (pinfunction "14_26") (pintype "passive"))
    )
    (net (code "34") (name "/LCD_TCON1") (class "Default")
      (node (ref "X6") (pin "29") (pinfunction "15_29") (pintype "passive"))
    )
    (net (code "35") (name "/LCD_TCON2") (class "Default")
      (node (ref "X6") (pin "28") (pinfunction "15_28") (pintype "passive"))
    )
    (net (code "36") (name "/MIC1_N") (class "Default")
      (node (ref "M1") (pin "1") (pinfunction "Out_1") (pintype "passive"))
    )
    (net (code "37") (name "/MICBIAS1") (class "Default")
      (node (ref "M1") (pin "3") (pinfunction "VDD_3") (pintype "passive"))
      (node (ref "M4") (pin "1") (pinfunction "VDD_1") (pintype "passive"))
    )
    (net (code "38") (name "/MIC_I2S_SCK") (class "Default")
      (node (ref "M2") (pin "4") (pinfunction "SCK_4") (pintype "passive"))
    )
    (net (code "39") (name "/MIC_I2S_SD") (class "Default")
      (node (ref "M2") (pin "6") (pinfunction "SD_6") (pintype "passive"))
    )
    (net (code "40") (name "/MIC_I2S_WS") (class "Default")
      (node (ref "M2") (pin "1") (pinfunction "WS_1") (pintype "passive"))
    )
    (net (code "41") (name "/MIC_OUT1") (class "Default")
      (node (ref "M4") (pin "3") (pinfunction "Out+_3") (pintype "passive"))
    )
    (net (code "42") (name "/MISO8") (class "Default")
      (node (ref "U7") (pin "7") (pinfunction "SDO_7") (pintype "output"))
    )
    (net (code "43") (name "/MOSI8") (class "Default")
      (node (ref "U7") (pin "9") (pinfunction "SDI_9") (pintype "input"))
      (node (ref "U8") (pin "2") (pinfunction "DIN_2") (pintype "passive"))
    )
    (net (code "44") (name "/SCK8") (class "Default")
      (node (ref "U7") (pin "8") (pinfunction "SCK_8") (pintype "input"))
      (node (ref "U8") (pin "5") (pinfunction "SCLK_5") (pintype "passive"))
    )
    (net (code "45") (name "/SCL") (class "Default")
      (node (ref "X6") (pin "40") (pinfunction "21_40") (pintype "passive"))
    )
    (net (code "46") (name "/SD0CLK") (class "Default")
      (node (ref "U24") (pin "15") (pinfunction "2A3_15") (pintype "bidirectional"))
    )
    (net (code "47") (name "/SD0DAT0") (class "Default")
      (node (ref "U24") (pin "17") (pinfunction "2A4_17") (pintype "bidirectional"))
    )
    (net (code "48") (name "/SD0DAT1") (class "Default")
      (node (ref "U24") (pin "8") (pinfunction "1A4_8") (pintype "bidirectional"))
    )
    (net (code "49") (name "/SD0DAT2") (class "Default")
      (node (ref "U24") (pin "6") (pinfunction "1A3_6") (pintype "bidirectional"))
    )
    (net (code "50") (name "/SD0DAT3") (class "Default")
      (node (ref "U24") (pin "11") (pinfunction "2A1_11") (pintype "bidirectional"))
    )
    (net (code "51") (name "/SD0SMD") (class "Default")
      (node (ref "U24") (pin "13") (pinfunction "2A2_13") (pintype "bidirectional"))
    )
    (net (code "52") (name "/SDA") (class "Default")
      (node (ref "X6") (pin "38") (pinfunction "20_38") (pintype "passive"))
    )
    (net (code "53") (name "/SDRAM_A1") (class "Default")
      (node (ref "U25") (pin "H7") (pinfunction "A0_H7") (pintype "input"))
    )
    (net (code "54") (name "/SDRAM_A2") (class "Default")
      (node (ref "U25") (pin "H8") (pinfunction "A1_H8") (pintype "input"))
    )
    (net (code "55") (name "/SDRAM_A3") (class "Default")
      (node (ref "U25") (pin "J8") (pinfunction "A2_J8") (pintype "input"))
    )
    (net (code "56") (name "/SDRAM_A4") (class "Default")
      (node (ref "U25") (pin "J7") (pinfunction "A3_J7") (pintype "input"))
    )
    (net (code "57") (name "/SDRAM_A5") (class "Default")
      (node (ref "U25") (pin "J3") (pinfunction "A4_J3") (pintype "input"))
    )
    (net (code "58") (name "/SDRAM_A6") (class "Default")
      (node (ref "U25") (pin "J2") (pinfunction "A5_J2") (pintype "input"))
    )
    (net (code "59") (name "/SDRAM_A7") (class "Default")
      (node (ref "U25") (pin "H3") (pinfunction "A6_H3") (pintype "input"))
    )
    (net (code "60") (name "/SDRAM_A8") (class "Default")
      (node (ref "U25") (pin "H2") (pinfunction "A7_H2") (pintype "input"))
    )
    (net (code "61") (name "/SDRAM_A9") (class "Default")
      (node (ref "U25") (pin "H1") (pinfunction "A8_H1") (pintype "input"))
    )
    (net (code "62") (name "/SDRAM_A10") (class "Default")
      (node (ref "U25") (pin "G3") (pinfunction "A9_G3") (pintype "input"))
    )
    (net (code "63") (name "/SDRAM_A11") (class "Default")
      (node (ref "U25") (pin "H9") (pinfunction "A10_H9") (pintype "input"))
    )
    (net (code "64") (name "/SDRAM_A12") (class "Default")
      (node (ref "U25") (pin "G2") (pinfunction "A11_G2") (pintype "input"))
    )
    (net (code "65") (name "/SDRAM_A13") (class "Default")
      (node (ref "U25") (pin "G7") (pinfunction "BA0_G7") (pintype "input"))
    )
    (net (code "66") (name "/SDRAM_A14") (class "Default")
      (node (ref "U25") (pin "G8") (pinfunction "BA1_G8") (pintype "input"))
    )
    (net (code "67") (name "/SDRAM_A15") (class "Default")
      (node (ref "U25") (pin "G1") (pinfunction "A12_G1") (pintype "input"))
    )
    (net (code "68") (name "/SDRAM_CAS#") (class "Default")
      (node (ref "U25") (pin "F7") (pinfunction "~{CAS}_F7") (pintype "input"))
    )
    (net (code "69") (name "/SDRAM_DQ10") (class "Default")
      (node (ref "U25") (pin "D1") (pinfunction "DQ10_D1") (pintype "bidirectional"))
    )
    (net (code "70") (name "/SDRAM_DQ11") (class "Default")
      (node (ref "U25") (pin "C2") (pinfunction "DQ11_C2") (pintype "bidirectional"))
    )
    (net (code "71") (name "/SDRAM_DQ12") (class "Default")
      (node (ref "U25") (pin "C1") (pinfunction "DQ12_C1") (pintype "bidirectional"))
    )
    (net (code "72") (name "/SDRAM_DQ13") (class "Default")
      (node (ref "U25") (pin "B2") (pinfunction "DQ13_B2") (pintype "bidirectional"))
    )
    (net (code "73") (name "/SDRAM_DQ14") (class "Default")
      (node (ref "U25") (pin "B1") (pinfunction "DQ14_B1") (pintype "bidirectional"))
    )
    (net (code "74") (name "/SDRAM_PWR_GOOD") (class "Default")
      (node (ref "U5") (pin "7") (pinfunction "PG_7") (pintype "passive"))
    )
    (net (code "75") (name "/SDRAM_SDCLK") (class "Default")
      (node (ref "U25") (pin "F2") (pinfunction "CLK_F2") (pintype "input"))
    )
    (net (code "76") (name "/SDRAM_SDCS#") (class "Default")
      (node (ref "U25") (pin "G9") (pinfunction "~{CS}_G9") (pintype "input"))
    )
    (net (code "77") (name "/SPI1_CLK") (class "Default")
      (node (ref "X6") (pin "47") (pinfunction "24_47") (pintype "passive"))
    )
    (net (code "78") (name "/SPI1_MISO") (class "Default")
      (node (ref "X6") (pin "41") (pinfunction "21_41") (pintype "passive"))
    )
    (net (code "79") (name "/SPI1_MOSI") (class "Default")
      (node (ref "X6") (pin "43") (pinfunction "22_43") (pintype "passive"))
    )
    (net (code "80") (name "/SPI1_SS2") (class "Default")
      (node (ref "X6") (pin "44") (pinfunction "23_44") (pintype "passive"))
    )
    (net (code "81") (name "/TOUCH_IRQ") (class "Default")
      (node (ref "X6") (pin "36") (pinfunction "19_36") (pintype "passive"))
    )
    (net (code "82") (name "/TOUCH_RST") (class "Default")
      (node (ref "X6") (pin "37") (pinfunction "19_37") (pintype "passive"))
    )
    (net (code "83") (name "/USBHS_N") (class "Default")
      (node (ref "U26") (pin "1") (pinfunction "1_1") (pintype "passive"))
      (node (ref "X3") (pin "2") (pinfunction "D-_2") (pintype "bidirectional"))
    )
    (net (code "84") (name "/USBHS_P") (class "Default")
      (node (ref "U26") (pin "2") (pinfunction "2_2") (pintype "passive"))
      (node (ref "X3") (pin "3") (pinfunction "D+_3") (pintype "bidirectional"))
    )
    (net (code "85") (name "GND") (class "Default")
      (node (ref "C109") (pin "2") (pinfunction "2_2") (pintype "passive"))
      (node (ref "C110") (pin "1") (pinfunction "1_1") (pintype "passive"))
      (node (ref "C111") (pin "2") (pinfunction "2_2") (pintype "passive"))
      (node (ref "C112") (pin "2") (pinfunction "2_2") (pintype "passive"))
      (node (ref "C113") (pin "2") (pinfunction "2_2") (pintype "passive"))
      (node (ref "C114") (pin "2") (pinfunction "2_2") (pintype "passive"))
      (node (ref "C115") (pin "2") (pinfunction "2_2") (pintype "passive"))
      (node (ref "C116") (pin "2") (pinfunction "2_2") (pintype "passive"))
      (node (ref "C117") (pin "2") (pinfunction "2_2") (pintype "passive"))
      (node (ref "C118") (pin "1") (pinfunction "1_1") (pintype "passive"))
      (node (ref "C119") (pin "2") (pinfunction "2_2") (pintype "passive"))
      (node (ref "C120") (pin "2") (pinfunction "2_2") (pintype "passive"))
      (node (ref "C121") (pin "2") (pinfunction "2_2") (pintype "passive"))
      (node (ref "C122") (pin "2") (pinfunction "2_2") (pintype "passive"))
      (node (ref "C123") (pin "1") (pinfunction "1_1") (pintype "passive"))
      (node (ref "C34") (pin "1") (pinfunction "1_1") (pintype "passive"))
      (node (ref "C35") (pin "2") (pinfunction "2_2") (pintype "passive"))
      (node (ref "C36") (pin "2") (pinfunction "2_2") (pintype "passive"))
      (node (ref "C37") (pin "2") (pinfunction "2_2") (pintype "passive"))
      (node (ref "C38") (pin "2") (pinfunction "2_2") (pintype "passive"))
      (node (ref "C41") (pin "2") (pinfunction "2_2") (pintype "passive"))
      (node (ref "C42") (pin "2") (pinfunction "2_2") (pintype "passive"))
      (node (ref "C43") (pin "2") (pinfunction "2_2") (pintype "passive"))
      (node (ref "C44") (pin "2") (pinfunction "2_2") (pintype "passive"))
      (node (ref "C45") (pin "2") (pinfunction "2_2") (pintype "passive"))
      (node (ref "C46") (pin "2") (pinfunction "2_2") (pintype "passive"))
      (node (ref "C47") (pin "2") (pinfunction "2_2") (pintype "passive"))
      (node (ref "C48") (pin "1") (pinfunction "1_1") (pintype "passive"))
      (node (ref "C49") (pin "2") (pinfunction "2_2") (pintype "passive"))
      (node (ref "C50") (pin "1") (pinfunction "1_1") (pintype "passive"))
      (node (ref "M1") (pin "2") (pinfunction "GND_2") (pintype "passive"))
      (node (ref "M2") (pin "2") (pinfunction "LR_2") (pintype "passive"))
      (node (ref "M2") (pin "3") (pinfunction "GND_3") (pintype "passive"))
      (node (ref "M3") (pin "4") (pinfunction "GND_4") (pintype "passive"))
      (node (ref "M4") (pin "4") (pinfunction "GND_4") (pintype "passive"))
      (node (ref "R24") (pin "2") (pinfunction "2_2") (pintype "passive"))
      (node (ref "R25") (pin "1") (pinfunction "1_1") (pintype "passive"))
      (node (ref "U24") (pin "10") (pinfunction "GND_10") (pintype "power_in"))
      (node (ref "U24") (pin "PAD") (pinfunction "PAD_PAD") (pintype "passive"))
      (node (ref "U25") (pin "A1") (pinfunction "VSS_A1") (pintype "power_in"))
      (node (ref "U25") (pin "A3") (pinfunction "VSSQ_A3") (pintype "power_in"))
      (node (ref "U25") (pin "B7") (pinfunction "VSSQ_B7") (pintype "power_in"))
      (node (ref "U25") (pin "C3") (pinfunction "VSSQ_C3") (pintype "power_in"))
      (node (ref "U25") (pin "D7") (pinfunction "VSSQ_D7") (pintype "power_in"))
      (node (ref "U25") (pin "E3") (pinfunction "VSS_E3") (pintype "power_in"))
      (node (ref "U25") (pin "J1") (pinfunction "VSS_J1") (pintype "power_in"))
      (node (ref "U26") (pin "7") (pinfunction "7_7") (pintype "passive"))
      (node (ref "U27") (pin "2") (pinfunction "GND_2") (pintype "power_in"))
      (node (ref "U27") (pin "5") (pinfunction "EP_5") (pintype "power_in"))
      (node (ref "U5") (pin "13") (pinfunction "EP_13") (pintype "passive"))
      (node (ref "U5") (pin "3") (pinfunction "GND_3") (pintype "passive"))
      (node (ref "U6") (pin "A6") (pinfunction "VSS_A6") (pintype "power_in"))
      (node (ref "U6") (pin "C4") (pinfunction "VSSQ_C4") (pintype "power_in"))
      (node (ref "U6") (pin "E7") (pinfunction "VSS_E7") (pintype "power_in"))
      (node (ref "U6") (pin "G5") (pinfunction "VSS_G5") (pintype "power_in"))
      (node (ref "U6") (pin "H10") (pinfunction "VSS_H10") (pintype "power_in"))
      (node (ref "U6") (pin "K8") (pinfunction "VSS_K8") (pintype "power_in"))
      (node (ref "U6") (pin "N2") (pinfunction "VSSQ_N2") (pintype "power_in"))
      (node (ref "U6") (pin "N5") (pinfunction "VSSQ_N5") (pintype "power_in"))
      (node (ref "U6") (pin "P4") (pinfunction "VSSQ_P4") (pintype "power_in"))
      (node (ref "U6") (pin "P6") (pinfunction "VSSQ_P6") (pintype "power_in"))
      (node (ref "U7") (pin "4") (pinfunction "IN-_4") (pintype "input"))
      (node (ref "U7") (pin "5") (pinfunction "GND_5") (pintype "power_in"))
      (node (ref "U8") (pin "4") (pinfunction "GND_4") (pintype "passive"))
      (node (ref "U8") (pin "8") (pinfunction "L_8") (pintype "passive"))
      (node (ref "U9") (pin "2") (pinfunction "GND_2") (pintype "power_in"))
      (node (ref "X3") (pin "5") (pinfunction "GND_5") (pintype "power_in"))
      (node (ref "X3") (pin "G1") (pinfunction "CASE_G1") (pintype "power_in"))
      (node (ref "X6") (pin "1") (pinfunction "1_1") (pintype "passive"))
      (node (ref "X6") (pin "16") (pinfunction "9_16") (pintype "passive"))
      (node (ref "X6") (pin "17") (pinfunction "9_17") (pintype "passive"))
      (node (ref "X6") (pin "2") (pinfunction "2_2") (pintype "passive"))
      (node (ref "X6") (pin "23") (pinfunction "12_23") (pintype "passive"))
      (node (ref "X6") (pin "24") (pinfunction "13_24") (pintype "passive"))
      (node (ref "X6") (pin "27") (pinfunction "14_27") (pintype "passive"))
      (node (ref "X6") (pin "30") (pinfunction "16_30") (pintype "passive"))
      (node (ref "X6") (pin "31") (pinfunction "16_31") (pintype "passive"))
      (node (ref "X6") (pin "34") (pinfunction "18_34") (pintype "passive"))
      (node (ref "X6") (pin "39") (pinfunction "20_39") (pintype "passive"))
      (node (ref "X6") (pin "42") (pinfunction "22_42") (pintype "passive"))
      (node (ref "X6") (pin "45") (pinfunction "23_45") (pintype "passive"))
      (node (ref "X6") (pin "46") (pinfunction "24_46") (pintype "passive"))
      (node (ref "X6") (pin "48") (pinfunction "25_48") (pintype "passive"))
      (node (ref "X6") (pin "53") (pinfunction "27_53") (pintype "passive"))
      (node (ref "X6") (pin "54") (pinfunction "28_54") (pintype "passive"))
      (node (ref "X6") (pin "8") (pinfunction "5_8") (pintype "passive"))
      (node (ref "X6") (pin "9") (pinfunction "5_9") (pintype "passive"))
    )
    (net (code "86") (name "Net-(M3-Out-)") (class "Default")
      (node (ref "M3") (pin "2") (pinfunction "Out-_2") (pintype "passive"))
      (node (ref "U9") (pin "1") (pinfunction "IN+_1") (pintype "passive"))
    )
    (net (code "87") (name "Net-(M3-VDD)") (class "Default")
      (node (ref "C121") (pin "1") (pinfunction "1_1") (pintype "passive"))
      (node (ref "C122") (pin "1") (pinfunction "1_1") (pintype "passive"))
      (node (ref "M3") (pin "1") (pinfunction "VDD_1") (pintype "passive"))
      (node (ref "U27") (pin "1") (pinfunction "OUT_1") (pintype "power_in"))
      (node (ref "U7") (pin "1") (pinfunction "REF_1") (pintype "input"))
      (node (ref "U9") (pin "5") (pinfunction "VCC_5") (pintype "power_in"))
    )
    (net (code "88") (name "Net-(U5-CTRL)") (class "Default")
      (node (ref "C110") (pin "2") (pinfunction "2_2") (pintype "passive"))
      (node (ref "L8") (pin "1") (pinfunction "1_1") (pintype "passive"))
      (node (ref "U5") (pin "4") (pinfunction "CTRL_4") (pintype "passive"))
      (node (ref "U5") (pin "5") (pinfunction "VOUT_5") (pintype "passive"))
    )
    (net (code "89") (name "Net-(U5-SW)") (class "Default")
      (node (ref "L8") (pin "2") (pinfunction "2_2") (pintype "passive"))
      (node (ref "U5") (pin "2") (pinfunction "SW_2") (pintype "passive"))
    )
    (net (code "90") (name "Net-(U6-VDDI)") (class "Default")
      (node (ref "C111") (pin "1") (pinfunction "1_1") (pintype "passive"))
      (node (ref "C112") (pin "1") (pinfunction "1_1") (pintype "passive"))
      (node (ref "U6") (pin "C2") (pinfunction "VDDI_C2") (pintype "power_in"))
    )
    (net (code "91") (name "Net-(U7-IN+)") (class "Default")
      (node (ref "C50") (pin "2") (pinfunction "2_2") (pintype "passive"))
      (node (ref "R27") (pin "2") (pinfunction "2_2") (pintype "passive"))
      (node (ref "U7") (pin "3") (pinfunction "IN+_3") (pintype "input"))
    )
    (net (code "92") (name "Net-(U8-W)") (class "Default")
      (node (ref "C39") (pin "2") (pinfunction "2_2") (pintype "passive"))
      (node (ref "U8") (pin "6") (pinfunction "W_6") (pintype "passive"))
    )
    (net (code "93") (name "Net-(U9-IN-)") (class "Default")
      (node (ref "C39") (pin "1") (pinfunction "1_1") (pintype "passive"))
      (node (ref "C40") (pin "1") (pinfunction "1_1") (pintype "passive"))
      (node (ref "R25") (pin "2") (pinfunction "2_2") (pintype "passive"))
      (node (ref "R26") (pin "1") (pinfunction "1_1") (pintype "passive"))
      (node (ref "U9") (pin "3") (pinfunction "IN-_3") (pintype "passive"))
    )
    (net (code "94") (name "Net-(U9-OUT)") (class "Default")
      (node (ref "C40") (pin "2") (pinfunction "2_2") (pintype "passive"))
      (node (ref "R26") (pin "2") (pinfunction "2_2") (pintype "passive"))
      (node (ref "R27") (pin "1") (pinfunction "1_1") (pintype "passive"))
      (node (ref "U9") (pin "4") (pinfunction "OUT_4") (pintype "passive"))
    )
    (net (code "95") (name "Net-(U24-1B3)") (class "Default")
      (node (ref "R53") (pin "5") (pinfunction "5_5") (pintype "passive"))
      (node (ref "U24") (pin "14") (pinfunction "1B3_14") (pintype "bidirectional"))
      (node (ref "U6") (pin "A5") (pinfunction "DAT2_A5") (pintype "bidirectional"))
    )
    (net (code "96") (name "Net-(U24-1B4)") (class "Default")
      (node (ref "R53") (pin "6") (pinfunction "6_6") (pintype "passive"))
      (node (ref "U24") (pin "12") (pinfunction "1B4_12") (pintype "bidirectional"))
      (node (ref "U6") (pin "A4") (pinfunction "DAT1_A4") (pintype "bidirectional"))
    )
    (net (code "97") (name "Net-(U24-2B1)") (class "Default")
      (node (ref "R52") (pin "5") (pinfunction "5_5") (pintype "passive"))
      (node (ref "U24") (pin "9") (pinfunction "2B1_9") (pintype "bidirectional"))
      (node (ref "U6") (pin "B2") (pinfunction "DAT3_B2") (pintype "bidirectional"))
    )
    (net (code "98") (name "Net-(U24-2B2)") (class "Default")
      (node (ref "R52") (pin "6") (pinfunction "6_6") (pintype "passive"))
      (node (ref "U24") (pin "7") (pinfunction "2B2_7") (pintype "bidirectional"))
      (node (ref "U6") (pin "M5") (pinfunction "CMD_M5") (pintype "bidirectional"))
    )
    (net (code "99") (name "Net-(U24-2B3)") (class "Default")
      (node (ref "R52") (pin "7") (pinfunction "7_7") (pintype "passive"))
      (node (ref "U24") (pin "5") (pinfunction "2B3_5") (pintype "bidirectional"))
      (node (ref "U6") (pin "M6") (pinfunction "CLK_M6") (pintype "input"))
    )
    (net (code "100") (name "Net-(U24-2B4)") (class "Default")
      (node (ref "R52") (pin "8") (pinfunction "8_8") (pintype "passive"))
      (node (ref "U24") (pin "3") (pinfunction "2B4_3") (pintype "bidirectional"))
      (node (ref "U6") (pin "A3") (pinfunction "DAT0_A3") (pintype "bidirectional"))
    )
    (net (code "101") (name "Net-(X3-ID)") (class "Default")
      (node (ref "U26") (pin "3") (pinfunction "3_3") (pintype "passive"))
      (node (ref "X3") (pin "4") (pinfunction "ID_4") (pintype "passive"))
    )
    (net (code "102") (name "Net-(X3-VBUS)") (class "Default")
      (node (ref "C123") (pin "2") (pinfunction "2_2") (pintype "passive"))
      (node (ref "L18") (pin "1") (pinfunction "1_1") (pintype "passive"))
      (node (ref "U26") (pin "6") (pinfunction "6_6") (pintype "passive"))
      (node (ref "X3") (pin "1") (pinfunction "VBUS_1") (pintype "power_in"))
    )
    (net (code "103") (name "SYS_V") (class "Default")
      (node (ref "C34") (pin "2") (pinfunction "2_2") (pintype "passive"))
      (node (ref "U5") (pin "1") (pinfunction "VIN_1") (pintype "passive"))
      (node (ref "U5") (pin "10") (pinfunction "VSEL2_10") (pintype "passive"))
      (node (ref "U5") (pin "11") (pinfunction "VSEL1_11") (pintype "passive"))
      (node (ref "U5") (pin "8") (pinfunction "VSEL4_8") (pintype "passive"))
      (node (ref "U5") (pin "9") (pinfunction "VSEL3_9") (pintype "passive"))
      (node (ref "X6") (pin "57") (pinfunction "29_57") (pintype "passive"))
      (node (ref "X6") (pin "58") (pinfunction "30_58") (pintype "passive"))
      (node (ref "X6") (pin "59") (pinfunction "30_59") (pintype "passive"))
      (node (ref "X6") (pin "60") (pinfunction "31_60") (pintype "passive"))
    )
    (net (code "104") (name "VBUSH") (class "Default")
      (node (ref "L18") (pin "2") (pinfunction "2_2") (pintype "passive"))
    )
    (net (code "105") (name "unconnected-(M3-Out+-Pad3)") (class "Default")
      (node (ref "M3") (pin "3") (pinfunction "Out+_3") (pintype "passive"))
    )
    (net (code "106") (name "unconnected-(M4-Out--Pad2)") (class "Default")
      (node (ref "M4") (pin "2") (pinfunction "Out-_2") (pintype "passive"))
    )
    (net (code "107") (name "unconnected-(R24-Pad1)") (class "Default")
      (node (ref "R24") (pin "1") (pinfunction "1_1") (pintype "passive"))
    )
    (net (code "108") (name "unconnected-(R53-Pad7)") (class "Default")
      (node (ref "R53") (pin "7") (pinfunction "7_7") (pintype "passive"))
    )
    (net (code "109") (name "unconnected-(R53-Pad8)") (class "Default")
      (node (ref "R53") (pin "8") (pinfunction "8_8") (pintype "passive"))
    )
    (net (code "110") (name "unconnected-(U5-EN-Pad12)") (class "Default")
      (node (ref "U5") (pin "12") (pinfunction "EN_12") (pintype "passive"))
    )
    (net (code "111") (name "unconnected-(U6-DAT4-PadB3)") (class "Default")
      (node (ref "U6") (pin "B3") (pinfunction "DAT4_B3") (pintype "bidirectional"))
    )
    (net (code "112") (name "unconnected-(U6-DAT5-PadB4)") (class "Default")
      (node (ref "U6") (pin "B4") (pinfunction "DAT5_B4") (pintype "bidirectional"))
    )
    (net (code "113") (name "unconnected-(U6-DAT6-PadB5)") (class "Default")
      (node (ref "U6") (pin "B5") (pinfunction "DAT6_B5") (pintype "bidirectional"))
    )
    (net (code "114") (name "unconnected-(U6-DAT7-PadB6)") (class "Default")
      (node (ref "U6") (pin "B6") (pinfunction "DAT7_B6") (pintype "bidirectional"))
    )
    (net (code "115") (name "unconnected-(U6-DS-PadH5)") (class "Default")
      (node (ref "U6") (pin "H5") (pinfunction "DS_H5") (pintype "output"))
    )
    (net (code "116") (name "unconnected-(U8-H-Pad1)") (class "Default")
      (node (ref "U8") (pin "1") (pinfunction "H_1") (pintype "passive"))
    )
    (net (code "117") (name "unconnected-(U24-1A1-Pad2)") (class "Default")
      (node (ref "U24") (pin "2") (pinfunction "1A1_2") (pintype "bidirectional"))
    )
    (net (code "118") (name "unconnected-(U24-1A2-Pad4)") (class "Default")
      (node (ref "U24") (pin "4") (pinfunction "1A2_4") (pintype "bidirectional"))
    )
    (net (code "119") (name "unconnected-(U24-1B1-Pad18)") (class "Default")
      (node (ref "U24") (pin "18") (pinfunction "1B1_18") (pintype "bidirectional"))
    )
    (net (code "120") (name "unconnected-(U24-1B2-Pad16)") (class "Default")
      (node (ref "U24") (pin "16") (pinfunction "1B2_16") (pintype "bidirectional"))
    )
    (net (code "121") (name "unconnected-(U25-CKE-PadF3)") (class "Default")
      (node (ref "U25") (pin "F3") (pinfunction "CKE_F3") (pintype "input"))
    )
    (net (code "122") (name "unconnected-(U25-DQ0-PadA8)") (class "Default")
      (node (ref "U25") (pin "A8") (pinfunction "DQ0_A8") (pintype "bidirectional"))
    )
    (net (code "123") (name "unconnected-(U25-DQ1-PadB9)") (class "Default")
      (node (ref "U25") (pin "B9") (pinfunction "DQ1_B9") (pintype "bidirectional"))
    )
    (net (code "124") (name "unconnected-(U25-DQ2-PadB8)") (class "Default")
      (node (ref "U25") (pin "B8") (pinfunction "DQ2_B8") (pintype "bidirectional"))
    )
    (net (code "125") (name "unconnected-(U25-DQ3-PadC9)") (class "Default")
      (node (ref "U25") (pin "C9") (pinfunction "DQ3_C9") (pintype "bidirectional"))
    )
    (net (code "126") (name "unconnected-(U25-DQ4-PadC8)") (class "Default")
      (node (ref "U25") (pin "C8") (pinfunction "DQ4_C8") (pintype "bidirectional"))
    )
    (net (code "127") (name "unconnected-(U25-DQ5-PadD9)") (class "Default")
      (node (ref "U25") (pin "D9") (pinfunction "DQ5_D9") (pintype "bidirectional"))
    )
    (net (code "128") (name "unconnected-(U25-DQ6-PadD8)") (class "Default")
      (node (ref "U25") (pin "D8") (pinfunction "DQ6_D8") (pintype "bidirectional"))
    )
    (net (code "129") (name "unconnected-(U25-DQ7-PadE9)") (class "Default")
      (node (ref "U25") (pin "E9") (pinfunction "DQ7_E9") (pintype "bidirectional"))
    )
    (net (code "130") (name "unconnected-(U25-DQ8-PadE1)") (class "Default")
      (node (ref "U25") (pin "E1") (pinfunction "DQ8_E1") (pintype "bidirectional"))
    )
    (net (code "131") (name "unconnected-(U25-DQ9-PadD2)") (class "Default")
      (node (ref "U25") (pin "D2") (pinfunction "DQ9_D2") (pintype "bidirectional"))
    )
    (net (code "132") (name "unconnected-(U25-DQ15-PadA2)") (class "Default")
      (node (ref "U25") (pin "A2") (pinfunction "DQ15_A2") (pintype "bidirectional"))
    )
    (net (code "133") (name "unconnected-(U25-LDQM-PadE8)") (class "Default")
      (node (ref "U25") (pin "E8") (pinfunction "LDQM_E8") (pintype "input"))
    )
    (net (code "134") (name "unconnected-(U25-NC-PadE2)") (class "Default")
      (node (ref "U25") (pin "E2") (pinfunction "NC_E2") (pintype "passive"))
    )
    (net (code "135") (name "unconnected-(U25-UDQM-PadF1)") (class "Default")
      (node (ref "U25") (pin "F1") (pinfunction "UDQM_F1") (pintype "input"))
    )
    (net (code "136") (name "unconnected-(U25-~{RAS}-PadF8)") (class "Default")
      (node (ref "U25") (pin "F8") (pinfunction "~{RAS}_F8") (pintype "input"))
    )
    (net (code "137") (name "unconnected-(U25-~{WE}-PadF9)") (class "Default")
      (node (ref "U25") (pin "F9") (pinfunction "~{WE}_F9") (pintype "input"))
    )
  )
)
